# Digital__IO.net
KiCad netlist of a schematic drawn in Altium Designer
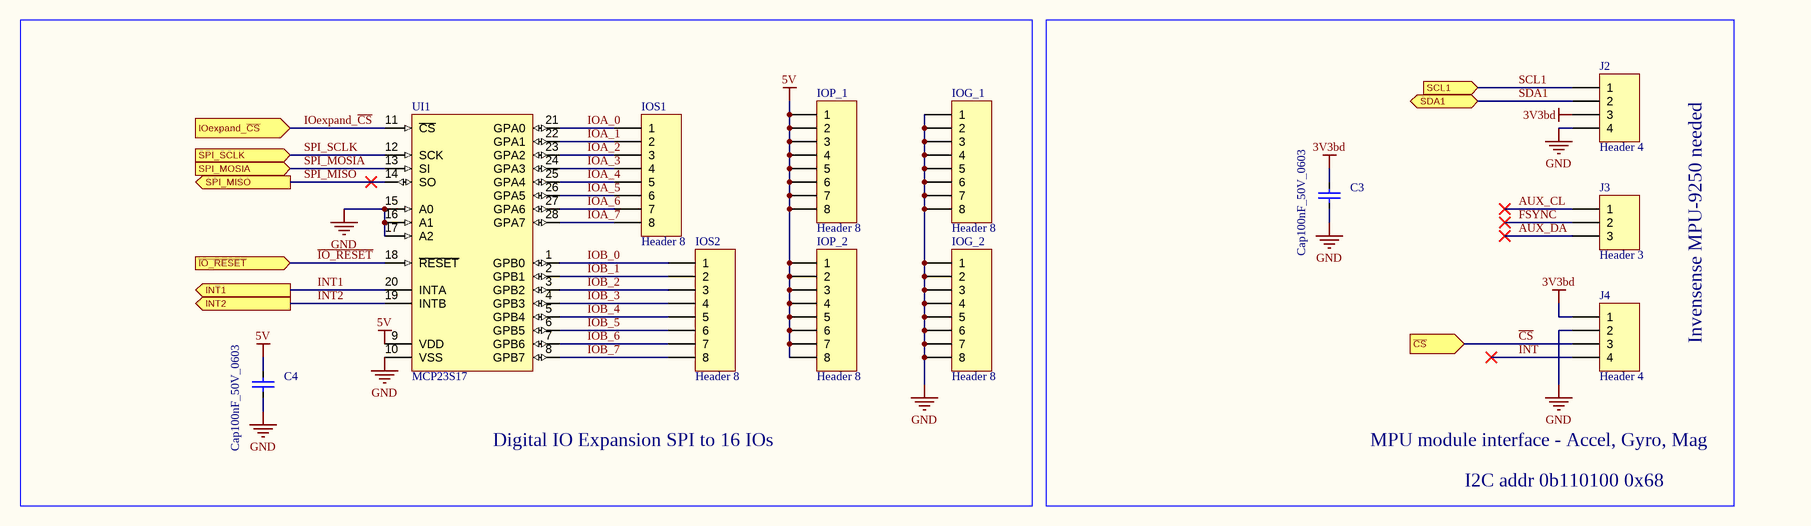
[diagram p0: Digital_ IO.SchDoc]

(export (version "E")
  (design (tool "Eeschema 10.0.6"))
  (components
    (comp (ref "C3")
      (value "Cap100nF_50V_0603")
      (footprint "0603C_L")
      (libsource (lib " Advanced] Training Course - A365") (part "CAP General"))
    )
    (comp (ref "C4")
      (value "Cap100nF_50V_0603")
      (footprint "0603C_L")
      (libsource (lib " Advanced] Training Course - A365") (part "CAP General"))
    )
    (comp (ref "IOG_1")
      (value "Header 8")
      (footprint "HDR1X8")
      (description "Header, 8-Pin")
      (fields (field (name "PUBLISHER") "Altium Limited"))
      (libsource (lib " Advanced] Training Course - A365") (part "Header 8"))
    )
    (comp (ref "IOG_2")
      (value "Header 8")
      (footprint "HDR1X8")
      (description "Header, 8-Pin")
      (fields (field (name "PUBLISHER") "Altium Limited"))
      (libsource (lib " Advanced] Training Course - A365") (part "Header 8"))
    )
    (comp (ref "IOP_1")
      (value "Header 8")
      (footprint "HDR1X8")
      (description "Header, 8-Pin")
      (fields (field (name "PUBLISHER") "Altium Limited"))
      (libsource (lib " Advanced] Training Course - A365") (part "Header 8"))
    )
    (comp (ref "IOP_2")
      (value "Header 8")
      (footprint "HDR1X8")
      (description "Header, 8-Pin")
      (fields (field (name "PUBLISHER") "Altium Limited"))
      (libsource (lib " Advanced] Training Course - A365") (part "Header 8"))
    )
    (comp (ref "IOS1")
      (value "Header 8")
      (footprint "HDR1X8")
      (description "Header, 8-Pin")
      (fields (field (name "PUBLISHER") "Altium Limited"))
      (libsource (lib " Advanced] Training Course - A365") (part "Header 8"))
    )
    (comp (ref "IOS2")
      (value "Header 8")
      (footprint "HDR1X8")
      (description "Header, 8-Pin")
      (fields (field (name "PUBLISHER") "Altium Limited"))
      (libsource (lib " Advanced] Training Course - A365") (part "Header 8"))
    )
    (comp (ref "J2")
      (value "Header 4")
      (footprint "HDR1X4")
      (description "Header, 4-Pin")
      (fields (field (name "PUBLISHER") "Altium Limited"))
      (libsource (lib " Advanced] Training Course - A365") (part "Header 4"))
    )
    (comp (ref "J3")
      (value "Header 3")
      (footprint "HDR1X3")
      (description "Header, 3-Pin")
      (fields (field (name "PUBLISHER") "Altium Limited"))
      (libsource (lib " Advanced] Training Course - A365") (part "Header 3"))
    )
    (comp (ref "J4")
      (value "Header 4")
      (footprint "HDR1X4")
      (description "Header, 4-Pin")
      (fields (field (name "PUBLISHER") "Altium Limited"))
      (libsource (lib " Advanced] Training Course - A365") (part "Header 4"))
    )
    (comp (ref "UI1")
      (value "MCP23S17")
      (footprint "SOIC-SO28_L")
      (description "16-Bit I/O Expander with Serial Interface, 28-Pin SOIC, Extended Temperature, Tape and Reel")
      (fields
        (field (name "MANUFACTURER") "Microchip")
        (field (name "MANUFACTURER PART NUMBER") "MCP23S17T-E/SO")
        (field (name "AVAILABLE PREVIEW IMAGES") "2D")
      )
      (libsource (lib " Advanced] Training Course - A365") (part "MCP23S17"))
    )
  )
  (nets
    (net (code "1") (name "/AUX_CL") (class "Default")
      (node (ref "J3") (pin "1") (pinfunction "1_1") (pintype "passive+no_connect"))
    )
    (net (code "2") (name "/AUX_DA") (class "Default")
      (node (ref "J3") (pin "3") (pinfunction "3_3") (pintype "passive+no_connect"))
    )
    (net (code "3") (name "/FSYNC") (class "Default")
      (node (ref "J3") (pin "2") (pinfunction "2_2") (pintype "passive+no_connect"))
    )
    (net (code "4") (name "/INT") (class "Default")
      (node (ref "J4") (pin "4") (pinfunction "4_4") (pintype "passive+no_connect"))
    )
    (net (code "5") (name "/INT1") (class "Default")
      (node (ref "UI1") (pin "20") (pinfunction "INTA_20") (pintype "open_collector"))
    )
    (net (code "6") (name "/INT2") (class "Default")
      (node (ref "UI1") (pin "19") (pinfunction "INTB_19") (pintype "open_collector"))
    )
    (net (code "7") (name "/IOA_0") (class "Default")
      (node (ref "IOS1") (pin "1") (pinfunction "1_1") (pintype "passive"))
      (node (ref "UI1") (pin "21") (pinfunction "GPA0_21") (pintype "bidirectional"))
    )
    (net (code "8") (name "/IOA_1") (class "Default")
      (node (ref "IOS1") (pin "2") (pinfunction "2_2") (pintype "passive"))
      (node (ref "UI1") (pin "22") (pinfunction "GPA1_22") (pintype "bidirectional"))
    )
    (net (code "9") (name "/IOA_2") (class "Default")
      (node (ref "IOS1") (pin "3") (pinfunction "3_3") (pintype "passive"))
      (node (ref "UI1") (pin "23") (pinfunction "GPA2_23") (pintype "bidirectional"))
    )
    (net (code "10") (name "/IOA_3") (class "Default")
      (node (ref "IOS1") (pin "4") (pinfunction "4_4") (pintype "passive"))
      (node (ref "UI1") (pin "24") (pinfunction "GPA3_24") (pintype "bidirectional"))
    )
    (net (code "11") (name "/IOA_4") (class "Default")
      (node (ref "IOS1") (pin "5") (pinfunction "5_5") (pintype "passive"))
      (node (ref "UI1") (pin "25") (pinfunction "GPA4_25") (pintype "bidirectional"))
    )
    (net (code "12") (name "/IOA_5") (class "Default")
      (node (ref "IOS1") (pin "6") (pinfunction "6_6") (pintype "passive"))
      (node (ref "UI1") (pin "26") (pinfunction "GPA5_26") (pintype "bidirectional"))
    )
    (net (code "13") (name "/IOA_6") (class "Default")
      (node (ref "IOS1") (pin "7") (pinfunction "7_7") (pintype "passive"))
      (node (ref "UI1") (pin "27") (pinfunction "GPA6_27") (pintype "bidirectional"))
    )
    (net (code "14") (name "/IOA_7") (class "Default")
      (node (ref "IOS1") (pin "8") (pinfunction "8_8") (pintype "passive"))
      (node (ref "UI1") (pin "28") (pinfunction "GPA7_28") (pintype "bidirectional"))
    )
    (net (code "15") (name "/IOB_0") (class "Default")
      (node (ref "IOS2") (pin "1") (pinfunction "1_1") (pintype "passive"))
      (node (ref "UI1") (pin "1") (pinfunction "GPB0_1") (pintype "bidirectional"))
    )
    (net (code "16") (name "/IOB_1") (class "Default")
      (node (ref "IOS2") (pin "2") (pinfunction "2_2") (pintype "passive"))
      (node (ref "UI1") (pin "2") (pinfunction "GPB1_2") (pintype "bidirectional"))
    )
    (net (code "17") (name "/IOB_2") (class "Default")
      (node (ref "IOS2") (pin "3") (pinfunction "3_3") (pintype "passive"))
      (node (ref "UI1") (pin "3") (pinfunction "GPB2_3") (pintype "bidirectional"))
    )
    (net (code "18") (name "/IOB_3") (class "Default")
      (node (ref "IOS2") (pin "4") (pinfunction "4_4") (pintype "passive"))
      (node (ref "UI1") (pin "4") (pinfunction "GPB3_4") (pintype "bidirectional"))
    )
    (net (code "19") (name "/IOB_4") (class "Default")
      (node (ref "IOS2") (pin "5") (pinfunction "5_5") (pintype "passive"))
      (node (ref "UI1") (pin "5") (pinfunction "GPB4_5") (pintype "bidirectional"))
    )
    (net (code "20") (name "/IOB_5") (class "Default")
      (node (ref "IOS2") (pin "6") (pinfunction "6_6") (pintype "passive"))
      (node (ref "UI1") (pin "6") (pinfunction "GPB5_6") (pintype "bidirectional"))
    )
    (net (code "21") (name "/IOB_6") (class "Default")
      (node (ref "IOS2") (pin "7") (pinfunction "7_7") (pintype "passive"))
      (node (ref "UI1") (pin "7") (pinfunction "GPB6_7") (pintype "bidirectional"))
    )
    (net (code "22") (name "/IOB_7") (class "Default")
      (node (ref "IOS2") (pin "8") (pinfunction "8_8") (pintype "passive"))
      (node (ref "UI1") (pin "8") (pinfunction "GPB7_8") (pintype "bidirectional"))
    )
    (net (code "23") (name "/IO_RESET") (class "Default")
      (node (ref "UI1") (pin "18") (pinfunction "~{RESET}_18") (pintype "input"))
    )
    (net (code "24") (name "/IOexpand_~{CS}") (class "Default")
      (node (ref "UI1") (pin "11") (pinfunction "~{CS}_11") (pintype "input"))
    )
    (net (code "25") (name "/SCL1") (class "Default")
      (node (ref "J2") (pin "1") (pinfunction "1_1") (pintype "passive"))
    )
    (net (code "26") (name "/SDA1") (class "Default")
      (node (ref "J2") (pin "2") (pinfunction "2_2") (pintype "passive"))
    )
    (net (code "27") (name "/SPI_MISO") (class "Default")
      (node (ref "UI1") (pin "14") (pinfunction "SO_14") (pintype "bidirectional"))
    )
    (net (code "28") (name "/SPI_MOSIA") (class "Default")
      (node (ref "UI1") (pin "13") (pinfunction "SI_13") (pintype "input"))
    )
    (net (code "29") (name "/SPI_SCLK") (class "Default")
      (node (ref "UI1") (pin "12") (pinfunction "SCK_12") (pintype "input"))
    )
    (net (code "30") (name "/~{CS}") (class "Default")
      (node (ref "J4") (pin "3") (pinfunction "3_3") (pintype "passive"))
    )
    (net (code "31") (name "3V3bd") (class "Default")
      (node (ref "C3") (pin "2") (pinfunction "2_2") (pintype "passive"))
      (node (ref "J2") (pin "3") (pinfunction "3_3") (pintype "passive"))
      (node (ref "J4") (pin "1") (pinfunction "1_1") (pintype "passive"))
    )
    (net (code "32") (name "5V") (class "Default")
      (node (ref "C4") (pin "2") (pinfunction "2_2") (pintype "passive"))
      (node (ref "IOP_1") (pin "1") (pinfunction "1_1") (pintype "passive"))
      (node (ref "IOP_1") (pin "2") (pinfunction "2_2") (pintype "passive"))
      (node (ref "IOP_1") (pin "3") (pinfunction "3_3") (pintype "passive"))
      (node (ref "IOP_1") (pin "4") (pinfunction "4_4") (pintype "passive"))
      (node (ref "IOP_1") (pin "5") (pinfunction "5_5") (pintype "passive"))
      (node (ref "IOP_1") (pin "6") (pinfunction "6_6") (pintype "passive"))
      (node (ref "IOP_1") (pin "7") (pinfunction "7_7") (pintype "passive"))
      (node (ref "IOP_1") (pin "8") (pinfunction "8_8") (pintype "passive"))
      (node (ref "IOP_2") (pin "1") (pinfunction "1_1") (pintype "passive"))
      (node (ref "IOP_2") (pin "2") (pinfunction "2_2") (pintype "passive"))
      (node (ref "IOP_2") (pin "3") (pinfunction "3_3") (pintype "passive"))
      (node (ref "IOP_2") (pin "4") (pinfunction "4_4") (pintype "passive"))
      (node (ref "IOP_2") (pin "5") (pinfunction "5_5") (pintype "passive"))
      (node (ref "IOP_2") (pin "6") (pinfunction "6_6") (pintype "passive"))
      (node (ref "IOP_2") (pin "7") (pinfunction "7_7") (pintype "passive"))
      (node (ref "IOP_2") (pin "8") (pinfunction "8_8") (pintype "passive"))
      (node (ref "UI1") (pin "9") (pinfunction "VDD_9") (pintype "power_in"))
    )
    (net (code "33") (name "GND") (class "Default")
      (node (ref "C3") (pin "1") (pinfunction "1_1") (pintype "passive"))
      (node (ref "C4") (pin "1") (pinfunction "1_1") (pintype "passive"))
      (node (ref "IOG_1") (pin "1") (pinfunction "1_1") (pintype "passive"))
      (node (ref "IOG_1") (pin "2") (pinfunction "2_2") (pintype "passive"))
      (node (ref "IOG_1") (pin "3") (pinfunction "3_3") (pintype "passive"))
      (node (ref "IOG_1") (pin "4") (pinfunction "4_4") (pintype "passive"))
      (node (ref "IOG_1") (pin "5") (pinfunction "5_5") (pintype "passive"))
      (node (ref "IOG_1") (pin "6") (pinfunction "6_6") (pintype "passive"))
      (node (ref "IOG_1") (pin "7") (pinfunction "7_7") (pintype "passive"))
      (node (ref "IOG_1") (pin "8") (pinfunction "8_8") (pintype "passive"))
      (node (ref "IOG_2") (pin "1") (pinfunction "1_1") (pintype "passive"))
      (node (ref "IOG_2") (pin "2") (pinfunction "2_2") (pintype "passive"))
      (node (ref "IOG_2") (pin "3") (pinfunction "3_3") (pintype "passive"))
      (node (ref "IOG_2") (pin "4") (pinfunction "4_4") (pintype "passive"))
      (node (ref "IOG_2") (pin "5") (pinfunction "5_5") (pintype "passive"))
      (node (ref "IOG_2") (pin "6") (pinfunction "6_6") (pintype "passive"))
      (node (ref "IOG_2") (pin "7") (pinfunction "7_7") (pintype "passive"))
      (node (ref "IOG_2") (pin "8") (pinfunction "8_8") (pintype "passive"))
      (node (ref "J2") (pin "4") (pinfunction "4_4") (pintype "passive"))
      (node (ref "J4") (pin "2") (pinfunction "2_2") (pintype "passive"))
      (node (ref "UI1") (pin "10") (pinfunction "VSS_10") (pintype "power_in"))
      (node (ref "UI1") (pin "15") (pinfunction "A0_15") (pintype "input"))
      (node (ref "UI1") (pin "16") (pinfunction "A1_16") (pintype "input"))
      (node (ref "UI1") (pin "17") (pinfunction "A2_17") (pintype "input"))
    )
  )
)
